# FPGA_GPIO.net
KiCad netlist of a schematic drawn in Altium Designer
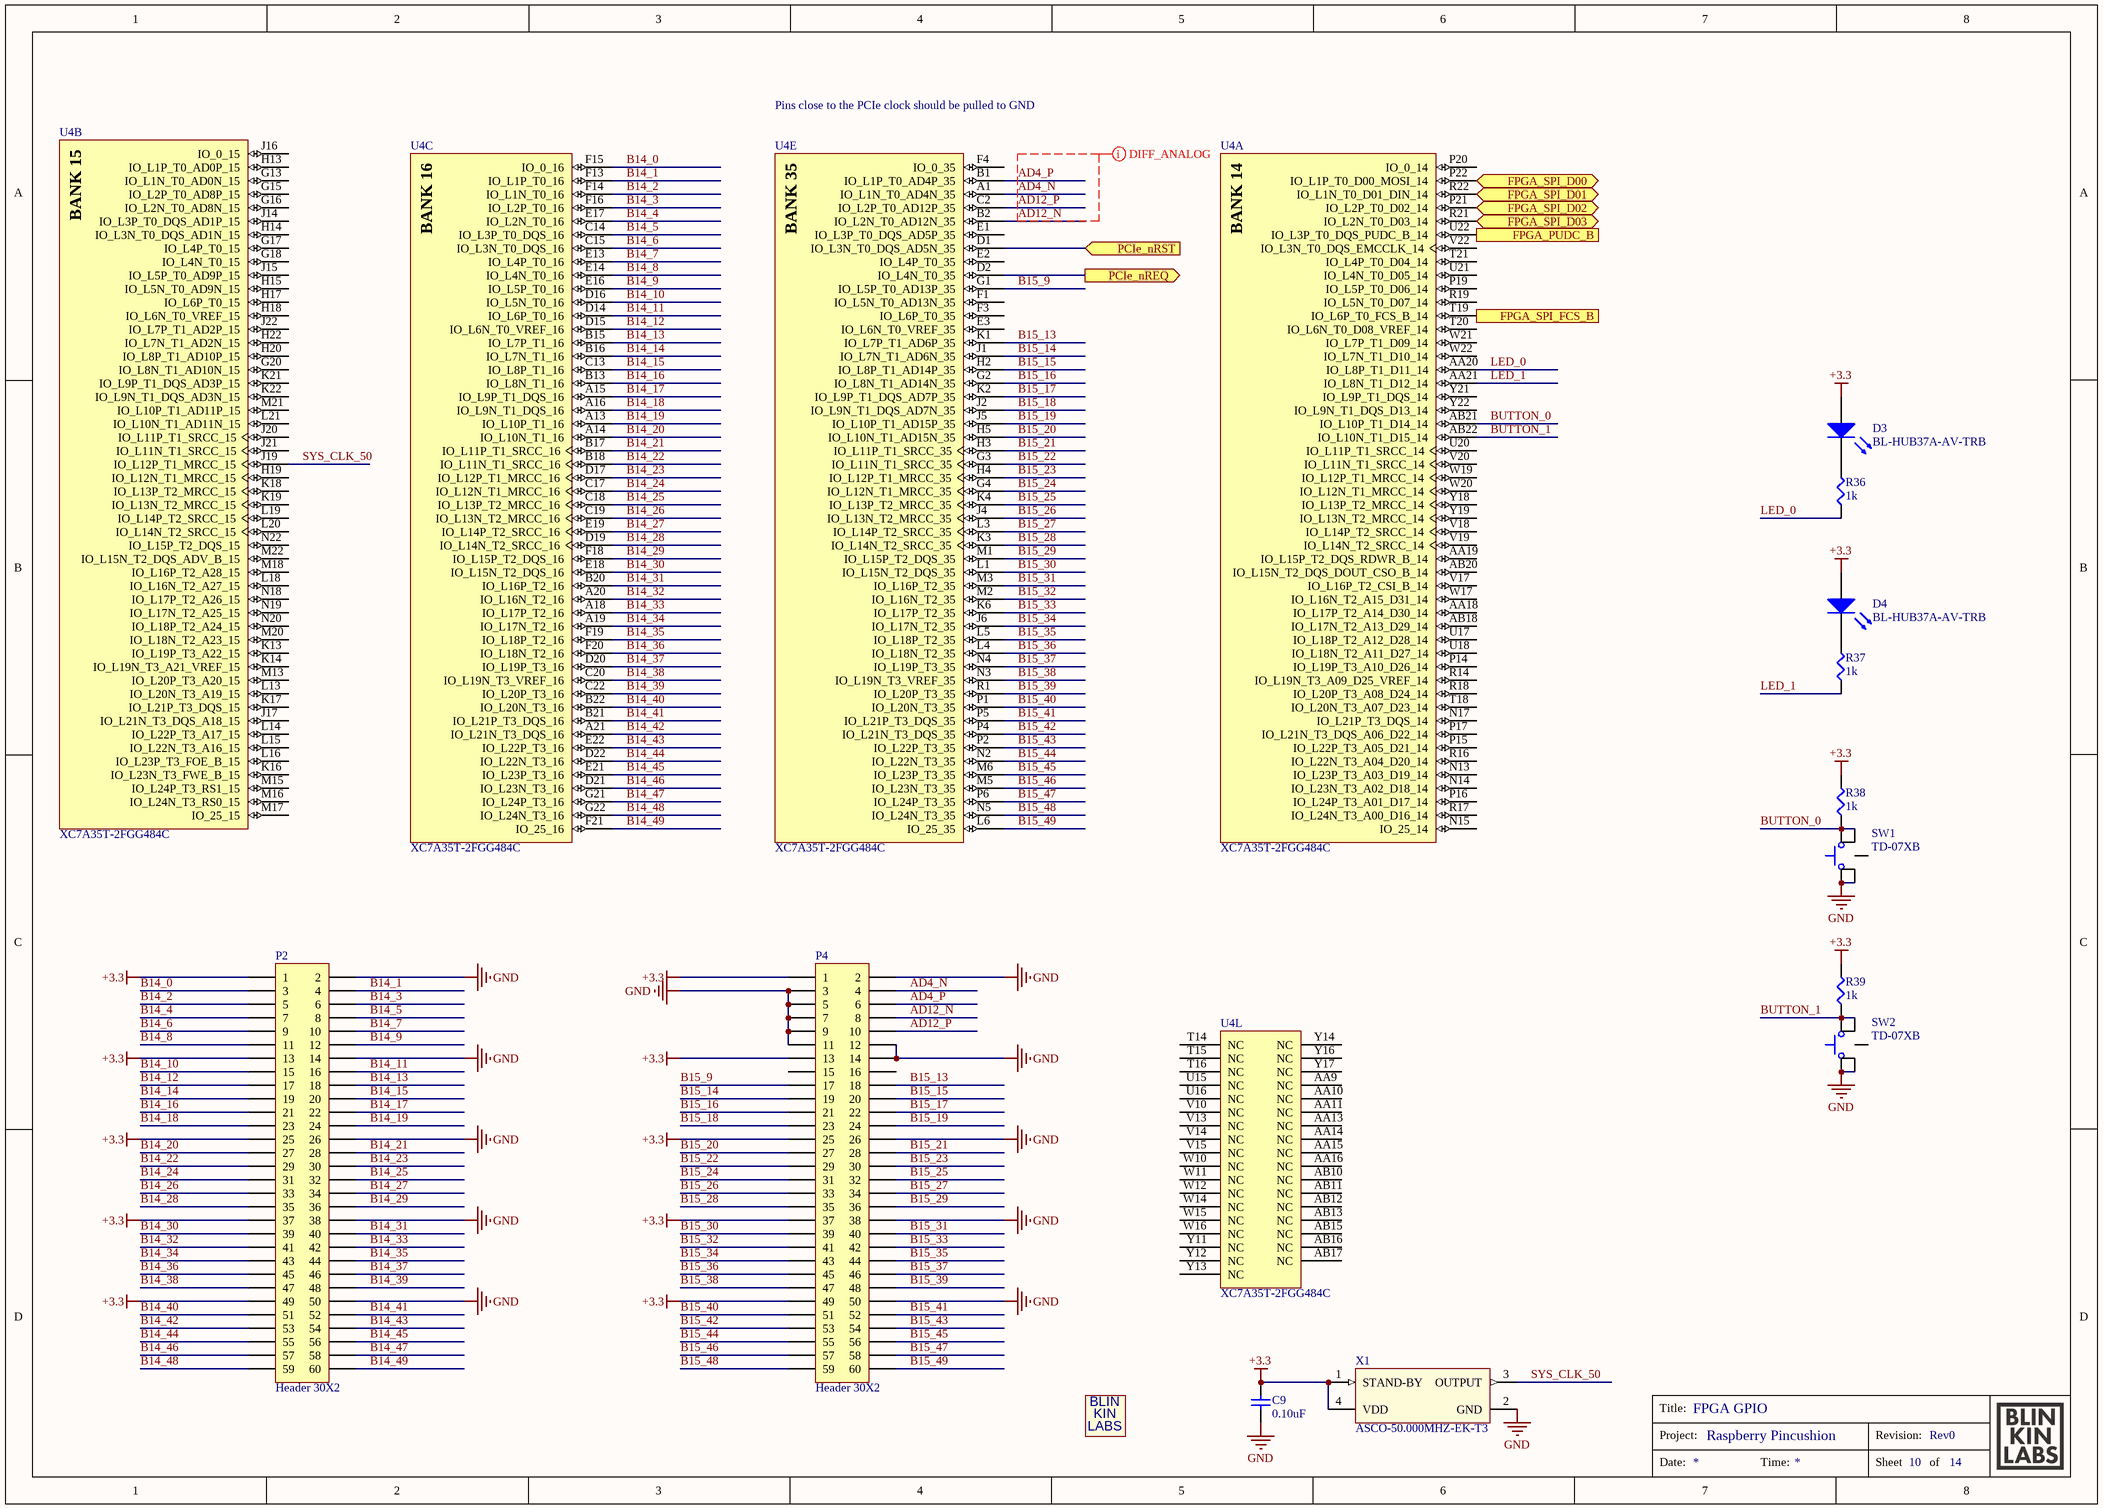
[diagram p0: FPGA GPIO.SchDoc]

(export (version "E")
  (design (tool "Eeschema 10.0.6"))
  (components
    (comp (ref "C9")
      (value "0.10uF")
      (footprint "CAPC1005X06L")
      (description "CAP CER 0.1UF 10V X5R 0402")
      (fields
        (field (name "PARTNUMBER") "GRM155R61A104KA01D")
        (field (name "DIGI-KEY PART NUMBER") "490-1318-1-ND")
      )
      (libsource (lib "cap_murata") (part "CAPACITOR"))
    )
    (comp (ref "D3")
      (value "BL-HUB37A-AV-TRB")
      (footprint "BL-Hxx37A-AV-TRB")
      (description "LED, 0402, Super Red, 50mcd@20mA, 627~637nm")
      (fields (field (name "MANUFACTURER") "BrtLed(佰鸿)") (field (name "LCSC PARTNUMBER") "C165980"))
      (libsource (lib "Blinkinlabs") (part "BL-HUB37A-AV-TRB"))
    )
    (comp (ref "D4")
      (value "BL-HUB37A-AV-TRB")
      (footprint "BL-Hxx37A-AV-TRB")
      (description "LED, 0402, Super Red, 50mcd@20mA, 627~637nm")
      (fields (field (name "MANUFACTURER") "BrtLed(佰鸿)") (field (name "LCSC PARTNUMBER") "C165980"))
      (libsource (lib "Blinkinlabs") (part "BL-HUB37A-AV-TRB"))
    )
    (comp (ref "L1")
      (value "BLINKINLABS_LOGO")
      (footprint "BLINKINLABS_LOGO")
      (description "Square logo")
      (libsource (lib "Blinkinlabs") (part "BLINKINLABS_LOGO"))
    )
    (comp (ref "P2")
      (value "Header 30X2")
      (footprint "HDR2X30")
      (description "Header, 30-Pin, Dual row")
      (fields (field (name "PUBLISHER") "Altium Limited"))
      (libsource (lib "Miscellaneous Connectors") (part "Header 30X2"))
    )
    (comp (ref "P4")
      (value "Header 30X2")
      (footprint "HDR2X30")
      (description "Header, 30-Pin, Dual row")
      (fields (field (name "PUBLISHER") "Altium Limited"))
      (libsource (lib "Miscellaneous Connectors") (part "Header 30X2"))
    )
    (comp (ref "R36")
      (value "1k")
      (footprint "ERJ2G(0402)_L")
      (description "RES SMD 1K OHM 5% 1/10W 0402")
      (fields (field (name "PARTNUMBER") "ERJ-2GEJ102X") (field (name "DIGI-KEY PART NUMBER") "P1.0KJCT-ND"))
      (libsource (lib "res_panasonic_erj_xls") (part "RESISTOR"))
    )
    (comp (ref "R37")
      (value "1k")
      (footprint "ERJ2G(0402)_L")
      (description "RES SMD 1K OHM 5% 1/10W 0402")
      (fields (field (name "PARTNUMBER") "ERJ-2GEJ102X") (field (name "DIGI-KEY PART NUMBER") "P1.0KJCT-ND"))
      (libsource (lib "res_panasonic_erj_xls") (part "RESISTOR"))
    )
    (comp (ref "R38")
      (value "1k")
      (footprint "ERJ2G(0402)_L")
      (description "RES SMD 1K OHM 5% 1/10W 0402")
      (fields (field (name "PARTNUMBER") "ERJ-2GEJ102X") (field (name "DIGI-KEY PART NUMBER") "P1.0KJCT-ND"))
      (libsource (lib "res_panasonic_erj_xls") (part "RESISTOR"))
    )
    (comp (ref "R39")
      (value "1k")
      (footprint "ERJ2G(0402)_L")
      (description "RES SMD 1K OHM 5% 1/10W 0402")
      (fields (field (name "PARTNUMBER") "ERJ-2GEJ102X") (field (name "DIGI-KEY PART NUMBER") "P1.0KJCT-ND"))
      (libsource (lib "res_panasonic_erj_xls") (part "RESISTOR"))
    )
    (comp (ref "SW1")
      (value "TD-07XB")
      (footprint "TD-07XB")
      (description "Tact Switch")
      (fields (field (name "MANUFACTURER") "ShenZhen XieJia Electronics Co Ltd"))
      (libsource (lib "Blinkinlabs") (part "TD-07XB"))
    )
    (comp (ref "SW2")
      (value "TD-07XB")
      (footprint "TD-07XB")
      (description "Tact Switch")
      (fields (field (name "MANUFACTURER") "ShenZhen XieJia Electronics Co Ltd"))
      (libsource (lib "Blinkinlabs") (part "TD-07XB"))
    )
    (comp (ref "U4")
      (value "XC7A35T-2FGG484C")
      (footprint "FGG484")
      (description "Artix-7 FPGA, 250 User I/Os, 4 GTP, 484-Ball BGA, Speed Grade 2, Commercial Grade, Pb-Free")
      (fields (field (name "MANUFACTURER") "Xilinx"))
      (libsource (lib "Altium Content Vault") (part "XLNX-XC7A35T-FGG484"))
    )
    (comp (ref "X1")
      (value "ASCO-50.000MHZ-EK-T3")
      (footprint "ABRA-ASCO-50.000MHZ-EK-T3-4_V")
      (description "Crystal Clock Oscillator, 50 MHz, -20 to 70 degC, 1.6 x 1.2 x 0.7 mm SMD")
      (fields (field (name "MANUFACTURER") "Abracon"))
      (libsource (lib "Altium Content Vault") (part "ABRA-ASCO-50_000MHZ-EK-T3-4"))
    )
  )
  (nets
    (net (code "1") (name "+3.3") (class "Default")
      (node (ref "C9") (pin "2") (pinfunction "2_2") (pintype "passive"))
      (node (ref "D3") (pin "1") (pinfunction "1_1") (pintype "passive"))
      (node (ref "D4") (pin "1") (pinfunction "1_1") (pintype "passive"))
      (node (ref "P2") (pin "1") (pinfunction "1_1") (pintype "passive"))
      (node (ref "P2") (pin "13") (pinfunction "13_13") (pintype "passive"))
      (node (ref "P2") (pin "25") (pinfunction "25_25") (pintype "passive"))
      (node (ref "P2") (pin "37") (pinfunction "37_37") (pintype "passive"))
      (node (ref "P2") (pin "49") (pinfunction "49_49") (pintype "passive"))
      (node (ref "P4") (pin "1") (pinfunction "1_1") (pintype "passive"))
      (node (ref "P4") (pin "13") (pinfunction "13_13") (pintype "passive"))
      (node (ref "P4") (pin "25") (pinfunction "25_25") (pintype "passive"))
      (node (ref "P4") (pin "37") (pinfunction "37_37") (pintype "passive"))
      (node (ref "P4") (pin "49") (pinfunction "49_49") (pintype "passive"))
      (node (ref "R38") (pin "2") (pinfunction "2_2") (pintype "passive"))
      (node (ref "R39") (pin "2") (pinfunction "2_2") (pintype "passive"))
      (node (ref "X1") (pin "1") (pinfunction "STAND-BY_1") (pintype "input"))
      (node (ref "X1") (pin "4") (pinfunction "VDD_4") (pintype "power_in"))
    )
    (net (code "2") (name "/AD4_N") (class "Default")
      (node (ref "P4") (pin "4") (pinfunction "4_4") (pintype "passive"))
      (node (ref "U4") (pin "A1") (pinfunction "IO_L1N_T0_AD4N_35_A1") (pintype "bidirectional"))
    )
    (net (code "3") (name "/AD4_P") (class "Default")
      (node (ref "P4") (pin "6") (pinfunction "6_6") (pintype "passive"))
      (node (ref "U4") (pin "B1") (pinfunction "IO_L1P_T0_AD4P_35_B1") (pintype "bidirectional"))
    )
    (net (code "4") (name "/AD12_N") (class "Default")
      (node (ref "P4") (pin "8") (pinfunction "8_8") (pintype "passive"))
      (node (ref "U4") (pin "B2") (pinfunction "IO_L2N_T0_AD12N_35_B2") (pintype "bidirectional"))
    )
    (net (code "5") (name "/AD12_P") (class "Default")
      (node (ref "P4") (pin "10") (pinfunction "10_10") (pintype "passive"))
      (node (ref "U4") (pin "C2") (pinfunction "IO_L2P_T0_AD12P_35_C2") (pintype "bidirectional"))
    )
    (net (code "6") (name "/B14_0") (class "Default")
      (node (ref "P2") (pin "3") (pinfunction "3_3") (pintype "passive"))
      (node (ref "U4") (pin "F15") (pinfunction "IO_0_16_F15") (pintype "bidirectional"))
    )
    (net (code "7") (name "/B14_1") (class "Default")
      (node (ref "P2") (pin "4") (pinfunction "4_4") (pintype "passive"))
      (node (ref "U4") (pin "F13") (pinfunction "IO_L1P_T0_16_F13") (pintype "bidirectional"))
    )
    (net (code "8") (name "/B14_2") (class "Default")
      (node (ref "P2") (pin "5") (pinfunction "5_5") (pintype "passive"))
      (node (ref "U4") (pin "F14") (pinfunction "IO_L1N_T0_16_F14") (pintype "bidirectional"))
    )
    (net (code "9") (name "/B14_3") (class "Default")
      (node (ref "P2") (pin "6") (pinfunction "6_6") (pintype "passive"))
      (node (ref "U4") (pin "F16") (pinfunction "IO_L2P_T0_16_F16") (pintype "bidirectional"))
    )
    (net (code "10") (name "/B14_4") (class "Default")
      (node (ref "P2") (pin "7") (pinfunction "7_7") (pintype "passive"))
      (node (ref "U4") (pin "E17") (pinfunction "IO_L2N_T0_16_E17") (pintype "bidirectional"))
    )
    (net (code "11") (name "/B14_5") (class "Default")
      (node (ref "P2") (pin "8") (pinfunction "8_8") (pintype "passive"))
      (node (ref "U4") (pin "C14") (pinfunction "IO_L3P_T0_DQS_16_C14") (pintype "bidirectional"))
    )
    (net (code "12") (name "/B14_6") (class "Default")
      (node (ref "P2") (pin "9") (pinfunction "9_9") (pintype "passive"))
      (node (ref "U4") (pin "C15") (pinfunction "IO_L3N_T0_DQS_16_C15") (pintype "bidirectional"))
    )
    (net (code "13") (name "/B14_7") (class "Default")
      (node (ref "P2") (pin "10") (pinfunction "10_10") (pintype "passive"))
      (node (ref "U4") (pin "E13") (pinfunction "IO_L4P_T0_16_E13") (pintype "bidirectional"))
    )
    (net (code "14") (name "/B14_8") (class "Default")
      (node (ref "P2") (pin "11") (pinfunction "11_11") (pintype "passive"))
      (node (ref "U4") (pin "E14") (pinfunction "IO_L4N_T0_16_E14") (pintype "bidirectional"))
    )
    (net (code "15") (name "/B14_9") (class "Default")
      (node (ref "P2") (pin "12") (pinfunction "12_12") (pintype "passive"))
      (node (ref "U4") (pin "E16") (pinfunction "IO_L5P_T0_16_E16") (pintype "bidirectional"))
    )
    (net (code "16") (name "/B14_10") (class "Default")
      (node (ref "P2") (pin "15") (pinfunction "15_15") (pintype "passive"))
      (node (ref "U4") (pin "D16") (pinfunction "IO_L5N_T0_16_D16") (pintype "bidirectional"))
    )
    (net (code "17") (name "/B14_11") (class "Default")
      (node (ref "P2") (pin "16") (pinfunction "16_16") (pintype "passive"))
      (node (ref "U4") (pin "D14") (pinfunction "IO_L6P_T0_16_D14") (pintype "bidirectional"))
    )
    (net (code "18") (name "/B14_12") (class "Default")
      (node (ref "P2") (pin "17") (pinfunction "17_17") (pintype "passive"))
      (node (ref "U4") (pin "D15") (pinfunction "IO_L6N_T0_VREF_16_D15") (pintype "bidirectional"))
    )
    (net (code "19") (name "/B14_13") (class "Default")
      (node (ref "P2") (pin "18") (pinfunction "18_18") (pintype "passive"))
      (node (ref "U4") (pin "B15") (pinfunction "IO_L7P_T1_16_B15") (pintype "bidirectional"))
    )
    (net (code "20") (name "/B14_14") (class "Default")
      (node (ref "P2") (pin "19") (pinfunction "19_19") (pintype "passive"))
      (node (ref "U4") (pin "B16") (pinfunction "IO_L7N_T1_16_B16") (pintype "bidirectional"))
    )
    (net (code "21") (name "/B14_15") (class "Default")
      (node (ref "P2") (pin "20") (pinfunction "20_20") (pintype "passive"))
      (node (ref "U4") (pin "C13") (pinfunction "IO_L8P_T1_16_C13") (pintype "bidirectional"))
    )
    (net (code "22") (name "/B14_16") (class "Default")
      (node (ref "P2") (pin "21") (pinfunction "21_21") (pintype "passive"))
      (node (ref "U4") (pin "B13") (pinfunction "IO_L8N_T1_16_B13") (pintype "bidirectional"))
    )
    (net (code "23") (name "/B14_17") (class "Default")
      (node (ref "P2") (pin "22") (pinfunction "22_22") (pintype "passive"))
      (node (ref "U4") (pin "A15") (pinfunction "IO_L9P_T1_DQS_16_A15") (pintype "bidirectional"))
    )
    (net (code "24") (name "/B14_18") (class "Default")
      (node (ref "P2") (pin "23") (pinfunction "23_23") (pintype "passive"))
      (node (ref "U4") (pin "A16") (pinfunction "IO_L9N_T1_DQS_16_A16") (pintype "bidirectional"))
    )
    (net (code "25") (name "/B14_19") (class "Default")
      (node (ref "P2") (pin "24") (pinfunction "24_24") (pintype "passive"))
      (node (ref "U4") (pin "A13") (pinfunction "IO_L10P_T1_16_A13") (pintype "bidirectional"))
    )
    (net (code "26") (name "/B14_20") (class "Default")
      (node (ref "P2") (pin "27") (pinfunction "27_27") (pintype "passive"))
      (node (ref "U4") (pin "A14") (pinfunction "IO_L10N_T1_16_A14") (pintype "bidirectional"))
    )
    (net (code "27") (name "/B14_21") (class "Default")
      (node (ref "P2") (pin "28") (pinfunction "28_28") (pintype "passive"))
      (node (ref "U4") (pin "B17") (pinfunction "IO_L11P_T1_SRCC_16_B17") (pintype "bidirectional"))
    )
    (net (code "28") (name "/B14_22") (class "Default")
      (node (ref "P2") (pin "29") (pinfunction "29_29") (pintype "passive"))
      (node (ref "U4") (pin "B18") (pinfunction "IO_L11N_T1_SRCC_16_B18") (pintype "bidirectional"))
    )
    (net (code "29") (name "/B14_23") (class "Default")
      (node (ref "P2") (pin "30") (pinfunction "30_30") (pintype "passive"))
      (node (ref "U4") (pin "D17") (pinfunction "IO_L12P_T1_MRCC_16_D17") (pintype "bidirectional"))
    )
    (net (code "30") (name "/B14_24") (class "Default")
      (node (ref "P2") (pin "31") (pinfunction "31_31") (pintype "passive"))
      (node (ref "U4") (pin "C17") (pinfunction "IO_L12N_T1_MRCC_16_C17") (pintype "bidirectional"))
    )
    (net (code "31") (name "/B14_25") (class "Default")
      (node (ref "P2") (pin "32") (pinfunction "32_32") (pintype "passive"))
      (node (ref "U4") (pin "C18") (pinfunction "IO_L13P_T2_MRCC_16_C18") (pintype "bidirectional"))
    )
    (net (code "32") (name "/B14_26") (class "Default")
      (node (ref "P2") (pin "33") (pinfunction "33_33") (pintype "passive"))
      (node (ref "U4") (pin "C19") (pinfunction "IO_L13N_T2_MRCC_16_C19") (pintype "bidirectional"))
    )
    (net (code "33") (name "/B14_27") (class "Default")
      (node (ref "P2") (pin "34") (pinfunction "34_34") (pintype "passive"))
      (node (ref "U4") (pin "E19") (pinfunction "IO_L14P_T2_SRCC_16_E19") (pintype "bidirectional"))
    )
    (net (code "34") (name "/B14_28") (class "Default")
      (node (ref "P2") (pin "35") (pinfunction "35_35") (pintype "passive"))
      (node (ref "U4") (pin "D19") (pinfunction "IO_L14N_T2_SRCC_16_D19") (pintype "bidirectional"))
    )
    (net (code "35") (name "/B14_29") (class "Default")
      (node (ref "P2") (pin "36") (pinfunction "36_36") (pintype "passive"))
      (node (ref "U4") (pin "F18") (pinfunction "IO_L15P_T2_DQS_16_F18") (pintype "bidirectional"))
    )
    (net (code "36") (name "/B14_30") (class "Default")
      (node (ref "P2") (pin "39") (pinfunction "39_39") (pintype "passive"))
      (node (ref "U4") (pin "E18") (pinfunction "IO_L15N_T2_DQS_16_E18") (pintype "bidirectional"))
    )
    (net (code "37") (name "/B14_31") (class "Default")
      (node (ref "P2") (pin "40") (pinfunction "40_40") (pintype "passive"))
      (node (ref "U4") (pin "B20") (pinfunction "IO_L16P_T2_16_B20") (pintype "bidirectional"))
    )
    (net (code "38") (name "/B14_32") (class "Default")
      (node (ref "P2") (pin "41") (pinfunction "41_41") (pintype "passive"))
      (node (ref "U4") (pin "A20") (pinfunction "IO_L16N_T2_16_A20") (pintype "bidirectional"))
    )
    (net (code "39") (name "/B14_33") (class "Default")
      (node (ref "P2") (pin "42") (pinfunction "42_42") (pintype "passive"))
      (node (ref "U4") (pin "A18") (pinfunction "IO_L17P_T2_16_A18") (pintype "bidirectional"))
    )
    (net (code "40") (name "/B14_34") (class "Default")
      (node (ref "P2") (pin "43") (pinfunction "43_43") (pintype "passive"))
      (node (ref "U4") (pin "A19") (pinfunction "IO_L17N_T2_16_A19") (pintype "bidirectional"))
    )
    (net (code "41") (name "/B14_35") (class "Default")
      (node (ref "P2") (pin "44") (pinfunction "44_44") (pintype "passive"))
      (node (ref "U4") (pin "F19") (pinfunction "IO_L18P_T2_16_F19") (pintype "bidirectional"))
    )
    (net (code "42") (name "/B14_36") (class "Default")
      (node (ref "P2") (pin "45") (pinfunction "45_45") (pintype "passive"))
      (node (ref "U4") (pin "F20") (pinfunction "IO_L18N_T2_16_F20") (pintype "bidirectional"))
    )
    (net (code "43") (name "/B14_37") (class "Default")
      (node (ref "P2") (pin "46") (pinfunction "46_46") (pintype "passive"))
      (node (ref "U4") (pin "D20") (pinfunction "IO_L19P_T3_16_D20") (pintype "bidirectional"))
    )
    (net (code "44") (name "/B14_38") (class "Default")
      (node (ref "P2") (pin "47") (pinfunction "47_47") (pintype "passive"))
      (node (ref "U4") (pin "C20") (pinfunction "IO_L19N_T3_VREF_16_C20") (pintype "bidirectional"))
    )
    (net (code "45") (name "/B14_39") (class "Default")
      (node (ref "P2") (pin "48") (pinfunction "48_48") (pintype "passive"))
      (node (ref "U4") (pin "C22") (pinfunction "IO_L20P_T3_16_C22") (pintype "bidirectional"))
    )
    (net (code "46") (name "/B14_40") (class "Default")
      (node (ref "P2") (pin "51") (pinfunction "51_51") (pintype "passive"))
      (node (ref "U4") (pin "B22") (pinfunction "IO_L20N_T3_16_B22") (pintype "bidirectional"))
    )
    (net (code "47") (name "/B14_41") (class "Default")
      (node (ref "P2") (pin "52") (pinfunction "52_52") (pintype "passive"))
      (node (ref "U4") (pin "B21") (pinfunction "IO_L21P_T3_DQS_16_B21") (pintype "bidirectional"))
    )
    (net (code "48") (name "/B14_42") (class "Default")
      (node (ref "P2") (pin "53") (pinfunction "53_53") (pintype "passive"))
      (node (ref "U4") (pin "A21") (pinfunction "IO_L21N_T3_DQS_16_A21") (pintype "bidirectional"))
    )
    (net (code "49") (name "/B14_43") (class "Default")
      (node (ref "P2") (pin "54") (pinfunction "54_54") (pintype "passive"))
      (node (ref "U4") (pin "E22") (pinfunction "IO_L22P_T3_16_E22") (pintype "bidirectional"))
    )
    (net (code "50") (name "/B14_44") (class "Default")
      (node (ref "P2") (pin "55") (pinfunction "55_55") (pintype "passive"))
      (node (ref "U4") (pin "D22") (pinfunction "IO_L22N_T3_16_D22") (pintype "bidirectional"))
    )
    (net (code "51") (name "/B14_45") (class "Default")
      (node (ref "P2") (pin "56") (pinfunction "56_56") (pintype "passive"))
      (node (ref "U4") (pin "E21") (pinfunction "IO_L23P_T3_16_E21") (pintype "bidirectional"))
    )
    (net (code "52") (name "/B14_46") (class "Default")
      (node (ref "P2") (pin "57") (pinfunction "57_57") (pintype "passive"))
      (node (ref "U4") (pin "D21") (pinfunction "IO_L23N_T3_16_D21") (pintype "bidirectional"))
    )
    (net (code "53") (name "/B14_47") (class "Default")
      (node (ref "P2") (pin "58") (pinfunction "58_58") (pintype "passive"))
      (node (ref "U4") (pin "G21") (pinfunction "IO_L24P_T3_16_G21") (pintype "bidirectional"))
    )
    (net (code "54") (name "/B14_48") (class "Default")
      (node (ref "P2") (pin "59") (pinfunction "59_59") (pintype "passive"))
      (node (ref "U4") (pin "G22") (pinfunction "IO_L24N_T3_16_G22") (pintype "bidirectional"))
    )
    (net (code "55") (name "/B14_49") (class "Default")
      (node (ref "P2") (pin "60") (pinfunction "60_60") (pintype "passive"))
      (node (ref "U4") (pin "F21") (pinfunction "IO_25_16_F21") (pintype "bidirectional"))
    )
    (net (code "56") (name "/B15_9") (class "Default")
      (node (ref "P4") (pin "17") (pinfunction "17_17") (pintype "passive"))
      (node (ref "U4") (pin "G1") (pinfunction "IO_L5P_T0_AD13P_35_G1") (pintype "bidirectional"))
    )
    (net (code "57") (name "/B15_13") (class "Default")
      (node (ref "P4") (pin "18") (pinfunction "18_18") (pintype "passive"))
      (node (ref "U4") (pin "K1") (pinfunction "IO_L7P_T1_AD6P_35_K1") (pintype "bidirectional"))
    )
    (net (code "58") (name "/B15_14") (class "Default")
      (node (ref "P4") (pin "19") (pinfunction "19_19") (pintype "passive"))
      (node (ref "U4") (pin "J1") (pinfunction "IO_L7N_T1_AD6N_35_J1") (pintype "bidirectional"))
    )
    (net (code "59") (name "/B15_15") (class "Default")
      (node (ref "P4") (pin "20") (pinfunction "20_20") (pintype "passive"))
      (node (ref "U4") (pin "H2") (pinfunction "IO_L8P_T1_AD14P_35_H2") (pintype "bidirectional"))
    )
    (net (code "60") (name "/B15_16") (class "Default")
      (node (ref "P4") (pin "21") (pinfunction "21_21") (pintype "passive"))
      (node (ref "U4") (pin "G2") (pinfunction "IO_L8N_T1_AD14N_35_G2") (pintype "bidirectional"))
    )
    (net (code "61") (name "/B15_17") (class "Default")
      (node (ref "P4") (pin "22") (pinfunction "22_22") (pintype "passive"))
      (node (ref "U4") (pin "K2") (pinfunction "IO_L9P_T1_DQS_AD7P_35_K2") (pintype "bidirectional"))
    )
    (net (code "62") (name "/B15_18") (class "Default")
      (node (ref "P4") (pin "23") (pinfunction "23_23") (pintype "passive"))
      (node (ref "U4") (pin "J2") (pinfunction "IO_L9N_T1_DQS_AD7N_35_J2") (pintype "bidirectional"))
    )
    (net (code "63") (name "/B15_19") (class "Default")
      (node (ref "P4") (pin "24") (pinfunction "24_24") (pintype "passive"))
      (node (ref "U4") (pin "J5") (pinfunction "IO_L10P_T1_AD15P_35_J5") (pintype "bidirectional"))
    )
    (net (code "64") (name "/B15_20") (class "Default")
      (node (ref "P4") (pin "27") (pinfunction "27_27") (pintype "passive"))
      (node (ref "U4") (pin "H5") (pinfunction "IO_L10N_T1_AD15N_35_H5") (pintype "bidirectional"))
    )
    (net (code "65") (name "/B15_21") (class "Default")
      (node (ref "P4") (pin "28") (pinfunction "28_28") (pintype "passive"))
      (node (ref "U4") (pin "H3") (pinfunction "IO_L11P_T1_SRCC_35_H3") (pintype "bidirectional"))
    )
    (net (code "66") (name "/B15_22") (class "Default")
      (node (ref "P4") (pin "29") (pinfunction "29_29") (pintype "passive"))
      (node (ref "U4") (pin "G3") (pinfunction "IO_L11N_T1_SRCC_35_G3") (pintype "bidirectional"))
    )
    (net (code "67") (name "/B15_23") (class "Default")
      (node (ref "P4") (pin "30") (pinfunction "30_30") (pintype "passive"))
      (node (ref "U4") (pin "H4") (pinfunction "IO_L12P_T1_MRCC_35_H4") (pintype "bidirectional"))
    )
    (net (code "68") (name "/B15_24") (class "Default")
      (node (ref "P4") (pin "31") (pinfunction "31_31") (pintype "passive"))
      (node (ref "U4") (pin "G4") (pinfunction "IO_L12N_T1_MRCC_35_G4") (pintype "bidirectional"))
    )
    (net (code "69") (name "/B15_25") (class "Default")
      (node (ref "P4") (pin "32") (pinfunction "32_32") (pintype "passive"))
      (node (ref "U4") (pin "K4") (pinfunction "IO_L13P_T2_MRCC_35_K4") (pintype "bidirectional"))
    )
    (net (code "70") (name "/B15_26") (class "Default")
      (node (ref "P4") (pin "33") (pinfunction "33_33") (pintype "passive"))
      (node (ref "U4") (pin "J4") (pinfunction "IO_L13N_T2_MRCC_35_J4") (pintype "bidirectional"))
    )
    (net (code "71") (name "/B15_27") (class "Default")
      (node (ref "P4") (pin "34") (pinfunction "34_34") (pintype "passive"))
      (node (ref "U4") (pin "L3") (pinfunction "IO_L14P_T2_SRCC_35_L3") (pintype "bidirectional"))
    )
    (net (code "72") (name "/B15_28") (class "Default")
      (node (ref "P4") (pin "35") (pinfunction "35_35") (pintype "passive"))
      (node (ref "U4") (pin "K3") (pinfunction "IO_L14N_T2_SRCC_35_K3") (pintype "bidirectional"))
    )
    (net (code "73") (name "/B15_29") (class "Default")
      (node (ref "P4") (pin "36") (pinfunction "36_36") (pintype "passive"))
      (node (ref "U4") (pin "M1") (pinfunction "IO_L15P_T2_DQS_35_M1") (pintype "bidirectional"))
    )
    (net (code "74") (name "/B15_30") (class "Default")
      (node (ref "P4") (pin "39") (pinfunction "39_39") (pintype "passive"))
      (node (ref "U4") (pin "L1") (pinfunction "IO_L15N_T2_DQS_35_L1") (pintype "bidirectional"))
    )
    (net (code "75") (name "/B15_31") (class "Default")
      (node (ref "P4") (pin "40") (pinfunction "40_40") (pintype "passive"))
      (node (ref "U4") (pin "M3") (pinfunction "IO_L16P_T2_35_M3") (pintype "bidirectional"))
    )
    (net (code "76") (name "/B15_32") (class "Default")
      (node (ref "P4") (pin "41") (pinfunction "41_41") (pintype "passive"))
      (node (ref "U4") (pin "M2") (pinfunction "IO_L16N_T2_35_M2") (pintype "bidirectional"))
    )
    (net (code "77") (name "/B15_33") (class "Default")
      (node (ref "P4") (pin "42") (pinfunction "42_42") (pintype "passive"))
      (node (ref "U4") (pin "K6") (pinfunction "IO_L17P_T2_35_K6") (pintype "bidirectional"))
    )
    (net (code "78") (name "/B15_34") (class "Default")
      (node (ref "P4") (pin "43") (pinfunction "43_43") (pintype "passive"))
      (node (ref "U4") (pin "J6") (pinfunction "IO_L17N_T2_35_J6") (pintype "bidirectional"))
    )
    (net (code "79") (name "/B15_35") (class "Default")
      (node (ref "P4") (pin "44") (pinfunction "44_44") (pintype "passive"))
      (node (ref "U4") (pin "L5") (pinfunction "IO_L18P_T2_35_L5") (pintype "bidirectional"))
    )
    (net (code "80") (name "/B15_36") (class "Default")
      (node (ref "P4") (pin "45") (pinfunction "45_45") (pintype "passive"))
      (node (ref "U4") (pin "L4") (pinfunction "IO_L18N_T2_35_L4") (pintype "bidirectional"))
    )
    (net (code "81") (name "/B15_37") (class "Default")
      (node (ref "P4") (pin "46") (pinfunction "46_46") (pintype "passive"))
      (node (ref "U4") (pin "N4") (pinfunction "IO_L19P_T3_35_N4") (pintype "bidirectional"))
    )
    (net (code "82") (name "/B15_38") (class "Default")
      (node (ref "P4") (pin "47") (pinfunction "47_47") (pintype "passive"))
      (node (ref "U4") (pin "N3") (pinfunction "IO_L19N_T3_VREF_35_N3") (pintype "bidirectional"))
    )
    (net (code "83") (name "/B15_39") (class "Default")
      (node (ref "P4") (pin "48") (pinfunction "48_48") (pintype "passive"))
      (node (ref "U4") (pin "R1") (pinfunction "IO_L20P_T3_35_R1") (pintype "bidirectional"))
    )
    (net (code "84") (name "/B15_40") (class "Default")
      (node (ref "P4") (pin "51") (pinfunction "51_51") (pintype "passive"))
      (node (ref "U4") (pin "P1") (pinfunction "IO_L20N_T3_35_P1") (pintype "bidirectional"))
    )
    (net (code "85") (name "/B15_41") (class "Default")
      (node (ref "P4") (pin "52") (pinfunction "52_52") (pintype "passive"))
      (node (ref "U4") (pin "P5") (pinfunction "IO_L21P_T3_DQS_35_P5") (pintype "bidirectional"))
    )
    (net (code "86") (name "/B15_42") (class "Default")
      (node (ref "P4") (pin "53") (pinfunction "53_53") (pintype "passive"))
      (node (ref "U4") (pin "P4") (pinfunction "IO_L21N_T3_DQS_35_P4") (pintype "bidirectional"))
    )
    (net (code "87") (name "/B15_43") (class "Default")
      (node (ref "P4") (pin "54") (pinfunction "54_54") (pintype "passive"))
      (node (ref "U4") (pin "P2") (pinfunction "IO_L22P_T3_35_P2") (pintype "bidirectional"))
    )
    (net (code "88") (name "/B15_44") (class "Default")
      (node (ref "P4") (pin "55") (pinfunction "55_55") (pintype "passive"))
      (node (ref "U4") (pin "N2") (pinfunction "IO_L22N_T3_35_N2") (pintype "bidirectional"))
    )
    (net (code "89") (name "/B15_45") (class "Default")
      (node (ref "P4") (pin "56") (pinfunction "56_56") (pintype "passive"))
      (node (ref "U4") (pin "M6") (pinfunction "IO_L23P_T3_35_M6") (pintype "bidirectional"))
    )
    (net (code "90") (name "/B15_46") (class "Default")
      (node (ref "P4") (pin "57") (pinfunction "57_57") (pintype "passive"))
      (node (ref "U4") (pin "M5") (pinfunction "IO_L23N_T3_35_M5") (pintype "bidirectional"))
    )
    (net (code "91") (name "/B15_47") (class "Default")
      (node (ref "P4") (pin "58") (pinfunction "58_58") (pintype "passive"))
      (node (ref "U4") (pin "P6") (pinfunction "IO_L24P_T3_35_P6") (pintype "bidirectional"))
    )
    (net (code "92") (name "/B15_48") (class "Default")
      (node (ref "P4") (pin "59") (pinfunction "59_59") (pintype "passive"))
      (node (ref "U4") (pin "N5") (pinfunction "IO_L24N_T3_35_N5") (pintype "bidirectional"))
    )
    (net (code "93") (name "/B15_49") (class "Default")
      (node (ref "P4") (pin "60") (pinfunction "60_60") (pintype "passive"))
      (node (ref "U4") (pin "L6") (pinfunction "IO_25_35_L6") (pintype "bidirectional"))
    )
    (net (code "94") (name "/BUTTON_0") (class "Default")
      (node (ref "R38") (pin "1") (pinfunction "1_1") (pintype "passive"))
      (node (ref "SW1") (pin "3") (pinfunction "3_3") (pintype "passive"))
      (node (ref "SW1") (pin "4") (pinfunction "4_4") (pintype "passive"))
      (node (ref "U4") (pin "AB21") (pinfunction "IO_L10P_T1_D14_14_AB21") (pintype "bidirectional"))
    )
    (net (code "95") (name "/BUTTON_1") (class "Default")
      (node (ref "R39") (pin "1") (pinfunction "1_1") (pintype "passive"))
      (node (ref "SW2") (pin "3") (pinfunction "3_3") (pintype "passive"))
      (node (ref "SW2") (pin "4") (pinfunction "4_4") (pintype "passive"))
      (node (ref "U4") (pin "AB22") (pinfunction "IO_L10N_T1_D15_14_AB22") (pintype "bidirectional"))
    )
    (net (code "96") (name "/FPGA_PUDC_B") (class "Default")
      (node (ref "U4") (pin "U22") (pinfunction "IO_L3P_T0_DQS_PUDC_B_14_U22") (pintype "bidirectional"))
    )
    (net (code "97") (name "/FPGA_SPI_D00") (class "Default")
      (node (ref "U4") (pin "P22") (pinfunction "IO_L1P_T0_D00_MOSI_14_P22") (pintype "bidirectional"))
    )
    (net (code "98") (name "/FPGA_SPI_D01") (class "Default")
      (node (ref "U4") (pin "R22") (pinfunction "IO_L1N_T0_D01_DIN_14_R22") (pintype "bidirectional"))
    )
    (net (code "99") (name "/FPGA_SPI_D02") (class "Default")
      (node (ref "U4") (pin "P21") (pinfunction "IO_L2P_T0_D02_14_P21") (pintype "bidirectional"))
    )
    (net (code "100") (name "/FPGA_SPI_D03") (class "Default")
      (node (ref "U4") (pin "R21") (pinfunction "IO_L2N_T0_D03_14_R21") (pintype "bidirectional"))
    )
    (net (code "101") (name "/FPGA_SPI_FCS_B") (class "Default")
      (node (ref "U4") (pin "T19") (pinfunction "IO_L6P_T0_FCS_B_14_T19") (pintype "bidirectional"))
    )
    (net (code "102") (name "/LED_0") (class "Default")
      (node (ref "R36") (pin "1") (pinfunction "1_1") (pintype "passive"))
      (node (ref "U4") (pin "AA20") (pinfunction "IO_L8P_T1_D11_14_AA20") (pintype "bidirectional"))
    )
    (net (code "103") (name "/LED_1") (class "Default")
      (node (ref "R37") (pin "1") (pinfunction "1_1") (pintype "passive"))
      (node (ref "U4") (pin "AA21") (pinfunction "IO_L8N_T1_D12_14_AA21") (pintype "bidirectional"))
    )
    (net (code "104") (name "/PCIe_nREQ") (class "Default")
      (node (ref "U4") (pin "D2") (pinfunction "IO_L4N_T0_35_D2") (pintype "bidirectional"))
    )
    (net (code "105") (name "/PCIe_nRST") (class "Default")
      (node (ref "U4") (pin "D1") (pinfunction "IO_L3N_T0_DQS_AD5N_35_D1") (pintype "bidirectional"))
    )
    (net (code "106") (name "/SYS_CLK_50") (class "Default")
      (node (ref "U4") (pin "J19") (pinfunction "IO_L12P_T1_MRCC_15_J19") (pintype "bidirectional"))
      (node (ref "X1") (pin "3") (pinfunction "OUTPUT_3") (pintype "output"))
    )
    (net (code "107") (name "GND") (class "Default")
      (node (ref "C9") (pin "1") (pinfunction "1_1") (pintype "passive"))
      (node (ref "P2") (pin "14") (pinfunction "14_14") (pintype "passive"))
      (node (ref "P2") (pin "2") (pinfunction "2_2") (pintype "passive"))
      (node (ref "P2") (pin "26") (pinfunction "26_26") (pintype "passive"))
      (node (ref "P2") (pin "38") (pinfunction "38_38") (pintype "passive"))
      (node (ref "P2") (pin "50") (pinfunction "50_50") (pintype "passive"))
      (node (ref "P4") (pin "11") (pinfunction "11_11") (pintype "passive"))
      (node (ref "P4") (pin "12") (pinfunction "12_12") (pintype "passive"))
      (node (ref "P4") (pin "14") (pinfunction "14_14") (pintype "passive"))
      (node (ref "P4") (pin "2") (pinfunction "2_2") (pintype "passive"))
      (node (ref "P4") (pin "26") (pinfunction "26_26") (pintype "passive"))
      (node (ref "P4") (pin "3") (pinfunction "3_3") (pintype "passive"))
      (node (ref "P4") (pin "38") (pinfunction "38_38") (pintype "passive"))
      (node (ref "P4") (pin "5") (pinfunction "5_5") (pintype "passive"))
      (node (ref "P4") (pin "50") (pinfunction "50_50") (pintype "passive"))
      (node (ref "P4") (pin "7") (pinfunction "7_7") (pintype "passive"))
      (node (ref "P4") (pin "9") (pinfunction "9_9") (pintype "passive"))
      (node (ref "SW1") (pin "1") (pinfunction "1_1") (pintype "passive"))
      (node (ref "SW1") (pin "2") (pinfunction "2_2") (pintype "passive"))
      (node (ref "SW2") (pin "1") (pinfunction "1_1") (pintype "passive"))
      (node (ref "SW2") (pin "2") (pinfunction "2_2") (pintype "passive"))
      (node (ref "X1") (pin "2") (pinfunction "GND_2") (pintype "power_in"))
    )
    (net (code "108") (name "Net-(D3-Pad2)") (class "Default")
      (node (ref "D3") (pin "2") (pinfunction "2_2") (pintype "passive"))
      (node (ref "R36") (pin "2") (pinfunction "2_2") (pintype "passive"))
    )
    (net (code "109") (name "Net-(D4-Pad2)") (class "Default")
      (node (ref "D4") (pin "2") (pinfunction "2_2") (pintype "passive"))
      (node (ref "R37") (pin "2") (pinfunction "2_2") (pintype "passive"))
    )
    (net (code "110") (name "unconnected-(P4-Pad15)") (class "Default")
      (node (ref "P4") (pin "15") (pinfunction "15_15") (pintype "passive"))
    )
    (net (code "111") (name "unconnected-(P4-Pad16)") (class "Default")
      (node (ref "P4") (pin "16") (pinfunction "16_16") (pintype "passive"))
    )
    (net (code "112") (name "unconnected-(SW1-Pad5)") (class "Default")
      (node (ref "SW1") (pin "5") (pinfunction "5_5") (pintype "passive"))
    )
    (net (code "113") (name "unconnected-(SW2-Pad5)") (class "Default")
      (node (ref "SW2") (pin "5") (pinfunction "5_5") (pintype "passive"))
    )
    (net (code "114") (name "unconnected-(U4A-IO_0_14-PadP20)") (class "Default")
      (node (ref "U4") (pin "P20") (pinfunction "IO_0_14_P20") (pintype "bidirectional"))
    )
    (net (code "115") (name "unconnected-(U4A-IO_25_14-PadN15)") (class "Default")
      (node (ref "U4") (pin "N15") (pinfunction "IO_25_14_N15") (pintype "bidirectional"))
    )
    (net (code "116") (name "unconnected-(U4A-IO_L3N_T0_DQS_EMCCLK_14-PadV22)") (class "Default")
      (node (ref "U4") (pin "V22") (pinfunction "IO_L3N_T0_DQS_EMCCLK_14_V22") (pintype "bidirectional"))
    )
    (net (code "117") (name "unconnected-(U4A-IO_L4N_T0_D05_14-PadU21)") (class "Default")
      (node (ref "U4") (pin "U21") (pinfunction "IO_L4N_T0_D05_14_U21") (pintype "bidirectional"))
    )
    (net (code "118") (name "unconnected-(U4A-IO_L4P_T0_D04_14-PadT21)") (class "Default")
      (node (ref "U4") (pin "T21") (pinfunction "IO_L4P_T0_D04_14_T21") (pintype "bidirectional"))
    )
    (net (code "119") (name "unconnected-(U4A-IO_L5N_T0_D07_14-PadR19)") (class "Default")
      (node (ref "U4") (pin "R19") (pinfunction "IO_L5N_T0_D07_14_R19") (pintype "bidirectional"))
    )
    (net (code "120") (name "unconnected-(U4A-IO_L5P_T0_D06_14-PadP19)") (class "Default")
      (node (ref "U4") (pin "P19") (pinfunction "IO_L5P_T0_D06_14_P19") (pintype "bidirectional"))
    )
    (net (code "121") (name "unconnected-(U4A-IO_L6N_T0_D08_VREF_14-PadT20)") (class "Default")
      (node (ref "U4") (pin "T20") (pinfunction "IO_L6N_T0_D08_VREF_14_T20") (pintype "bidirectional"))
    )
    (net (code "122") (name "unconnected-(U4A-IO_L7N_T1_D10_14-PadW22)") (class "Default")
      (node (ref "U4") (pin "W22") (pinfunction "IO_L7N_T1_D10_14_W22") (pintype "bidirectional"))
    )
    (net (code "123") (name "unconnected-(U4A-IO_L7P_T1_D09_14-PadW21)") (class "Default")
      (node (ref "U4") (pin "W21") (pinfunction "IO_L7P_T1_D09_14_W21") (pintype "bidirectional"))
    )
    (net (code "124") (name "unconnected-(U4A-IO_L9N_T1_DQS_D13_14-PadY22)") (class "Default")
      (node (ref "U4") (pin "Y22") (pinfunction "IO_L9N_T1_DQS_D13_14_Y22") (pintype "bidirectional"))
    )
    (net (code "125") (name "unconnected-(U4A-IO_L9P_T1_DQS_14-PadY21)") (class "Default")
      (node (ref "U4") (pin "Y21") (pinfunction "IO_L9P_T1_DQS_14_Y21") (pintype "bidirectional"))
    )
    (net (code "126") (name "unconnected-(U4A-IO_L11N_T1_SRCC_14-PadV20)") (class "Default")
      (node (ref "U4") (pin "V20") (pinfunction "IO_L11N_T1_SRCC_14_V20") (pintype "bidirectional"))
    )
    (net (code "127") (name "unconnected-(U4A-IO_L11P_T1_SRCC_14-PadU20)") (class "Default")
      (node (ref "U4") (pin "U20") (pinfunction "IO_L11P_T1_SRCC_14_U20") (pintype "bidirectional"))
    )
    (net (code "128") (name "unconnected-(U4A-IO_L12N_T1_MRCC_14-PadW20)") (class "Default")
      (node (ref "U4") (pin "W20") (pinfunction "IO_L12N_T1_MRCC_14_W20") (pintype "bidirectional"))
    )
    (net (code "129") (name "unconnected-(U4A-IO_L12P_T1_MRCC_14-PadW19)") (class "Default")
      (node (ref "U4") (pin "W19") (pinfunction "IO_L12P_T1_MRCC_14_W19") (pintype "bidirectional"))
    )
    (net (code "130") (name "unconnected-(U4A-IO_L13N_T2_MRCC_14-PadY19)") (class "Default")
      (node (ref "U4") (pin "Y19") (pinfunction "IO_L13N_T2_MRCC_14_Y19") (pintype "bidirectional"))
    )
    (net (code "131") (name "unconnected-(U4A-IO_L13P_T2_MRCC_14-PadY18)") (class "Default")
      (node (ref "U4") (pin "Y18") (pinfunction "IO_L13P_T2_MRCC_14_Y18") (pintype "bidirectional"))
    )
    (net (code "132") (name "unconnected-(U4A-IO_L14N_T2_SRCC_14-PadV19)") (class "Default")
      (node (ref "U4") (pin "V19") (pinfunction "IO_L14N_T2_SRCC_14_V19") (pintype "bidirectional"))
    )
    (net (code "133") (name "unconnected-(U4A-IO_L14P_T2_SRCC_14-PadV18)") (class "Default")
      (node (ref "U4") (pin "V18") (pinfunction "IO_L14P_T2_SRCC_14_V18") (pintype "bidirectional"))
    )
    (net (code "134") (name "unconnected-(U4A-IO_L15N_T2_DQS_DOUT_CSO_B_14-PadAB20)") (class "Default")
      (node (ref "U4") (pin "AB20") (pinfunction "IO_L15N_T2_DQS_DOUT_CSO_B_14_AB20") (pintype "bidirectional"))
    )
    (net (code "135") (name "unconnected-(U4A-IO_L15P_T2_DQS_RDWR_B_14-PadAA19)") (class "Default")
      (node (ref "U4") (pin "AA19") (pinfunction "IO_L15P_T2_DQS_RDWR_B_14_AA19") (pintype "bidirectional"))
    )
    (net (code "136") (name "unconnected-(U4A-IO_L16N_T2_A15_D31_14-PadW17)") (class "Default")
      (node (ref "U4") (pin "W17") (pinfunction "IO_L16N_T2_A15_D31_14_W17") (pintype "bidirectional"))
    )
    (net (code "137") (name "unconnected-(U4A-IO_L16P_T2_CSI_B_14-PadV17)") (class "Default")
      (node (ref "U4") (pin "V17") (pinfunction "IO_L16P_T2_CSI_B_14_V17") (pintype "bidirectional"))
    )
    (net (code "138") (name "unconnected-(U4A-IO_L17N_T2_A13_D29_14-PadAB18)") (class "Default")
      (node (ref "U4") (pin "AB18") (pinfunction "IO_L17N_T2_A13_D29_14_AB18") (pintype "bidirectional"))
    )
    (net (code "139") (name "unconnected-(U4A-IO_L17P_T2_A14_D30_14-PadAA18)") (class "Default")
      (node (ref "U4") (pin "AA18") (pinfunction "IO_L17P_T2_A14_D30_14_AA18") (pintype "bidirectional"))
    )
    (net (code "140") (name "unconnected-(U4A-IO_L18N_T2_A11_D27_14-PadU18)") (class "Default")
      (node (ref "U4") (pin "U18") (pinfunction "IO_L18N_T2_A11_D27_14_U18") (pintype "bidirectional"))
    )
    (net (code "141") (name "unconnected-(U4A-IO_L18P_T2_A12_D28_14-PadU17)") (class "Default")
      (node (ref "U4") (pin "U17") (pinfunction "IO_L18P_T2_A12_D28_14_U17") (pintype "bidirectional"))
    )
    (net (code "142") (name "unconnected-(U4A-IO_L19N_T3_A09_D25_VREF_14-PadR14)") (class "Default")
      (node (ref "U4") (pin "R14") (pinfunction "IO_L19N_T3_A09_D25_VREF_14_R14") (pintype "bidirectional"))
    )
    (net (code "143") (name "unconnected-(U4A-IO_L19P_T3_A10_D26_14-PadP14)") (class "Default")
      (node (ref "U4") (pin "P14") (pinfunction "IO_L19P_T3_A10_D26_14_P14") (pintype "bidirectional"))
    )
    (net (code "144") (name "unconnected-(U4A-IO_L20N_T3_A07_D23_14-PadT18)") (class "Default")
      (node (ref "U4") (pin "T18") (pinfunction "IO_L20N_T3_A07_D23_14_T18") (pintype "bidirectional"))
    )
    (net (code "145") (name "unconnected-(U4A-IO_L20P_T3_A08_D24_14-PadR18)") (class "Default")
      (node (ref "U4") (pin "R18") (pinfunction "IO_L20P_T3_A08_D24_14_R18") (pintype "bidirectional"))
    )
    (net (code "146") (name "unconnected-(U4A-IO_L21N_T3_DQS_A06_D22_14-PadP17)") (class "Default")
      (node (ref "U4") (pin "P17") (pinfunction "IO_L21N_T3_DQS_A06_D22_14_P17") (pintype "bidirectional"))
    )
    (net (code "147") (name "unconnected-(U4A-IO_L21P_T3_DQS_14-PadN17)") (class "Default")
      (node (ref "U4") (pin "N17") (pinfunction "IO_L21P_T3_DQS_14_N17") (pintype "bidirectional"))
    )
    (net (code "148") (name "unconnected-(U4A-IO_L22N_T3_A04_D20_14-PadR16)") (class "Default")
      (node (ref "U4") (pin "R16") (pinfunction "IO_L22N_T3_A04_D20_14_R16") (pintype "bidirectional"))
    )
    (net (code "149") (name "unconnected-(U4A-IO_L22P_T3_A05_D21_14-PadP15)") (class "Default")
      (node (ref "U4") (pin "P15") (pinfunction "IO_L22P_T3_A05_D21_14_P15") (pintype "bidirectional"))
    )
    (net (code "150") (name "unconnected-(U4A-IO_L23N_T3_A02_D18_14-PadN14)") (class "Default")
      (node (ref "U4") (pin "N14") (pinfunction "IO_L23N_T3_A02_D18_14_N14") (pintype "bidirectional"))
    )
    (net (code "151") (name "unconnected-(U4A-IO_L23P_T3_A03_D19_14-PadN13)") (class "Default")
      (node (ref "U4") (pin "N13") (pinfunction "IO_L23P_T3_A03_D19_14_N13") (pintype "bidirectional"))
    )
    (net (code "152") (name "unconnected-(U4A-IO_L24N_T3_A00_D16_14-PadR17)") (class "Default")
      (node (ref "U4") (pin "R17") (pinfunction "IO_L24N_T3_A00_D16_14_R17") (pintype "bidirectional"))
    )
    (net (code "153") (name "unconnected-(U4A-IO_L24P_T3_A01_D17_14-PadP16)") (class "Default")
      (node (ref "U4") (pin "P16") (pinfunction "IO_L24P_T3_A01_D17_14_P16") (pintype "bidirectional"))
    )
    (net (code "154") (name "unconnected-(U4B-IO_0_15-PadJ16)") (class "Default")
      (node (ref "U4") (pin "J16") (pinfunction "IO_0_15_J16") (pintype "bidirectional"))
    )
    (net (code "155") (name "unconnected-(U4B-IO_25_15-PadM17)") (class "Default")
      (node (ref "U4") (pin "M17") (pinfunction "IO_25_15_M17") (pintype "bidirectional"))
    )
    (net (code "156") (name "unconnected-(U4B-IO_L1N_T0_AD0N_15-PadG13)") (class "Default")
      (node (ref "U4") (pin "G13") (pinfunction "IO_L1N_T0_AD0N_15_G13") (pintype "bidirectional"))
    )
    (net (code "157") (name "unconnected-(U4B-IO_L1P_T0_AD0P_15-PadH13)") (class "Default")
      (node (ref "U4") (pin "H13") (pinfunction "IO_L1P_T0_AD0P_15_H13") (pintype "bidirectional"))
    )
    (net (code "158") (name "unconnected-(U4B-IO_L2N_T0_AD8N_15-PadG16)") (class "Default")
      (node (ref "U4") (pin "G16") (pinfunction "IO_L2N_T0_AD8N_15_G16") (pintype "bidirectional"))
    )
    (net (code "159") (name "unconnected-(U4B-IO_L2P_T0_AD8P_15-PadG15)") (class "Default")
      (node (ref "U4") (pin "G15") (pinfunction "IO_L2P_T0_AD8P_15_G15") (pintype "bidirectional"))
    )
    (net (code "160") (name "unconnected-(U4B-IO_L3N_T0_DQS_AD1N_15-PadH14)") (class "Default")
      (node (ref "U4") (pin "H14") (pinfunction "IO_L3N_T0_DQS_AD1N_15_H14") (pintype "bidirectional"))
    )
    (net (code "161") (name "unconnected-(U4B-IO_L3P_T0_DQS_AD1P_15-PadJ14)") (class "Default")
      (node (ref "U4") (pin "J14") (pinfunction "IO_L3P_T0_DQS_AD1P_15_J14") (pintype "bidirectional"))
    )
    (net (code "162") (name "unconnected-(U4B-IO_L4N_T0_15-PadG18)") (class "Default")
      (node (ref "U4") (pin "G18") (pinfunction "IO_L4N_T0_15_G18") (pintype "bidirectional"))
    )
    (net (code "163") (name "unconnected-(U4B-IO_L4P_T0_15-PadG17)") (class "Default")
      (node (ref "U4") (pin "G17") (pinfunction "IO_L4P_T0_15_G17") (pintype "bidirectional"))
    )
    (net (code "164") (name "unconnected-(U4B-IO_L5N_T0_AD9N_15-PadH15)") (class "Default")
      (node (ref "U4") (pin "H15") (pinfunction "IO_L5N_T0_AD9N_15_H15") (pintype "bidirectional"))
    )
    (net (code "165") (name "unconnected-(U4B-IO_L5P_T0_AD9P_15-PadJ15)") (class "Default")
      (node (ref "U4") (pin "J15") (pinfunction "IO_L5P_T0_AD9P_15_J15") (pintype "bidirectional"))
    )
    (net (code "166") (name "unconnected-(U4B-IO_L6N_T0_VREF_15-PadH18)") (class "Default")
      (node (ref "U4") (pin "H18") (pinfunction "IO_L6N_T0_VREF_15_H18") (pintype "bidirectional"))
    )
    (net (code "167") (name "unconnected-(U4B-IO_L6P_T0_15-PadH17)") (class "Default")
      (node (ref "U4") (pin "H17") (pinfunction "IO_L6P_T0_15_H17") (pintype "bidirectional"))
    )
    (net (code "168") (name "unconnected-(U4B-IO_L7N_T1_AD2N_15-PadH22)") (class "Default")
      (node (ref "U4") (pin "H22") (pinfunction "IO_L7N_T1_AD2N_15_H22") (pintype "bidirectional"))
    )
    (net (code "169") (name "unconnected-(U4B-IO_L7P_T1_AD2P_15-PadJ22)") (class "Default")
      (node (ref "U4") (pin "J22") (pinfunction "IO_L7P_T1_AD2P_15_J22") (pintype "bidirectional"))
    )
    (net (code "170") (name "unconnected-(U4B-IO_L8N_T1_AD10N_15-PadG20)") (class "Default")
      (node (ref "U4") (pin "G20") (pinfunction "IO_L8N_T1_AD10N_15_G20") (pintype "bidirectional"))
    )
    (net (code "171") (name "unconnected-(U4B-IO_L8P_T1_AD10P_15-PadH20)") (class "Default")
      (node (ref "U4") (pin "H20") (pinfunction "IO_L8P_T1_AD10P_15_H20") (pintype "bidirectional"))
    )
    (net (code "172") (name "unconnected-(U4B-IO_L9N_T1_DQS_AD3N_15-PadK22)") (class "Default")
      (node (ref "U4") (pin "K22") (pinfunction "IO_L9N_T1_DQS_AD3N_15_K22") (pintype "bidirectional"))
    )
    (net (code "173") (name "unconnected-(U4B-IO_L9P_T1_DQS_AD3P_15-PadK21)") (class "Default")
      (node (ref "U4") (pin "K21") (pinfunction "IO_L9P_T1_DQS_AD3P_15_K21") (pintype "bidirectional"))
    )
    (net (code "174") (name "unconnected-(U4B-IO_L10N_T1_AD11N_15-PadL21)") (class "Default")
      (node (ref "U4") (pin "L21") (pinfunction "IO_L10N_T1_AD11N_15_L21") (pintype "bidirectional"))
    )
    (net (code "175") (name "unconnected-(U4B-IO_L10P_T1_AD11P_15-PadM21)") (class "Default")
      (node (ref "U4") (pin "M21") (pinfunction "IO_L10P_T1_AD11P_15_M21") (pintype "bidirectional"))
    )
    (net (code "176") (name "unconnected-(U4B-IO_L11N_T1_SRCC_15-PadJ21)") (class "Default")
      (node (ref "U4") (pin "J21") (pinfunction "IO_L11N_T1_SRCC_15_J21") (pintype "bidirectional"))
    )
    (net (code "177") (name "unconnected-(U4B-IO_L11P_T1_SRCC_15-PadJ20)") (class "Default")
      (node (ref "U4") (pin "J20") (pinfunction "IO_L11P_T1_SRCC_15_J20") (pintype "bidirectional"))
    )
    (net (code "178") (name "unconnected-(U4B-IO_L12N_T1_MRCC_15-PadH19)") (class "Default")
      (node (ref "U4") (pin "H19") (pinfunction "IO_L12N_T1_MRCC_15_H19") (pintype "bidirectional"))
    )
    (net (code "179") (name "unconnected-(U4B-IO_L13N_T2_MRCC_15-PadK19)") (class "Default")
      (node (ref "U4") (pin "K19") (pinfunction "IO_L13N_T2_MRCC_15_K19") (pintype "bidirectional"))
    )
    (net (code "180") (name "unconnected-(U4B-IO_L13P_T2_MRCC_15-PadK18)") (class "Default")
      (node (ref "U4") (pin "K18") (pinfunction "IO_L13P_T2_MRCC_15_K18") (pintype "bidirectional"))
    )
    (net (code "181") (name "unconnected-(U4B-IO_L14N_T2_SRCC_15-PadL20)") (class "Default")
      (node (ref "U4") (pin "L20") (pinfunction "IO_L14N_T2_SRCC_15_L20") (pintype "bidirectional"))
    )
    (net (code "182") (name "unconnected-(U4B-IO_L14P_T2_SRCC_15-PadL19)") (class "Default")
      (node (ref "U4") (pin "L19") (pinfunction "IO_L14P_T2_SRCC_15_L19") (pintype "bidirectional"))
    )
    (net (code "183") (name "unconnected-(U4B-IO_L15N_T2_DQS_ADV_B_15-PadM22)") (class "Default")
      (node (ref "U4") (pin "M22") (pinfunction "IO_L15N_T2_DQS_ADV_B_15_M22") (pintype "bidirectional"))
    )
    (net (code "184") (name "unconnected-(U4B-IO_L15P_T2_DQS_15-PadN22)") (class "Default")
      (node (ref "U4") (pin "N22") (pinfunction "IO_L15P_T2_DQS_15_N22") (pintype "bidirectional"))
    )
    (net (code "185") (name "unconnected-(U4B-IO_L16N_T2_A27_15-PadL18)") (class "Default")
      (node (ref "U4") (pin "L18") (pinfunction "IO_L16N_T2_A27_15_L18") (pintype "bidirectional"))
    )
    (net (code "186") (name "unconnected-(U4B-IO_L16P_T2_A28_15-PadM18)") (class "Default")
      (node (ref "U4") (pin "M18") (pinfunction "IO_L16P_T2_A28_15_M18") (pintype "bidirectional"))
    )
    (net (code "187") (name "unconnected-(U4B-IO_L17N_T2_A25_15-PadN19)") (class "Default")
      (node (ref "U4") (pin "N19") (pinfunction "IO_L17N_T2_A25_15_N19") (pintype "bidirectional"))
    )
    (net (code "188") (name "unconnected-(U4B-IO_L17P_T2_A26_15-PadN18)") (class "Default")
      (node (ref "U4") (pin "N18") (pinfunction "IO_L17P_T2_A26_15_N18") (pintype "bidirectional"))
    )
    (net (code "189") (name "unconnected-(U4B-IO_L18N_T2_A23_15-PadM20)") (class "Default")
      (node (ref "U4") (pin "M20") (pinfunction "IO_L18N_T2_A23_15_M20") (pintype "bidirectional"))
    )
    (net (code "190") (name "unconnected-(U4B-IO_L18P_T2_A24_15-PadN20)") (class "Default")
      (node (ref "U4") (pin "N20") (pinfunction "IO_L18P_T2_A24_15_N20") (pintype "bidirectional"))
    )
    (net (code "191") (name "unconnected-(U4B-IO_L19N_T3_A21_VREF_15-PadK14)") (class "Default")
      (node (ref "U4") (pin "K14") (pinfunction "IO_L19N_T3_A21_VREF_15_K14") (pintype "bidirectional"))
    )
    (net (code "192") (name "unconnected-(U4B-IO_L19P_T3_A22_15-PadK13)") (class "Default")
      (node (ref "U4") (pin "K13") (pinfunction "IO_L19P_T3_A22_15_K13") (pintype "bidirectional"))
    )
    (net (code "193") (name "unconnected-(U4B-IO_L20N_T3_A19_15-PadL13)") (class "Default")
      (node (ref "U4") (pin "L13") (pinfunction "IO_L20N_T3_A19_15_L13") (pintype "bidirectional"))
    )
    (net (code "194") (name "unconnected-(U4B-IO_L20P_T3_A20_15-PadM13)") (class "Default")
      (node (ref "U4") (pin "M13") (pinfunction "IO_L20P_T3_A20_15_M13") (pintype "bidirectional"))
    )
    (net (code "195") (name "unconnected-(U4B-IO_L21N_T3_DQS_A18_15-PadJ17)") (class "Default")
      (node (ref "U4") (pin "J17") (pinfunction "IO_L21N_T3_DQS_A18_15_J17") (pintype "bidirectional"))
    )
    (net (code "196") (name "unconnected-(U4B-IO_L21P_T3_DQS_15-PadK17)") (class "Default")
      (node (ref "U4") (pin "K17") (pinfunction "IO_L21P_T3_DQS_15_K17") (pintype "bidirectional"))
    )
    (net (code "197") (name "unconnected-(U4B-IO_L22N_T3_A16_15-PadL15)") (class "Default")
      (node (ref "U4") (pin "L15") (pinfunction "IO_L22N_T3_A16_15_L15") (pintype "bidirectional"))
    )
    (net (code "198") (name "unconnected-(U4B-IO_L22P_T3_A17_15-PadL14)") (class "Default")
      (node (ref "U4") (pin "L14") (pinfunction "IO_L22P_T3_A17_15_L14") (pintype "bidirectional"))
    )
    (net (code "199") (name "unconnected-(U4B-IO_L23N_T3_FWE_B_15-PadK16)") (class "Default")
      (node (ref "U4") (pin "K16") (pinfunction "IO_L23N_T3_FWE_B_15_K16") (pintype "bidirectional"))
    )
    (net (code "200") (name "unconnected-(U4B-IO_L23P_T3_FOE_B_15-PadL16)") (class "Default")
      (node (ref "U4") (pin "L16") (pinfunction "IO_L23P_T3_FOE_B_15_L16") (pintype "bidirectional"))
    )
    (net (code "201") (name "unconnected-(U4B-IO_L24N_T3_RS0_15-PadM16)") (class "Default")
      (node (ref "U4") (pin "M16") (pinfunction "IO_L24N_T3_RS0_15_M16") (pintype "bidirectional"))
    )
    (net (code "202") (name "unconnected-(U4B-IO_L24P_T3_RS1_15-PadM15)") (class "Default")
      (node (ref "U4") (pin "M15") (pinfunction "IO_L24P_T3_RS1_15_M15") (pintype "bidirectional"))
    )
    (net (code "203") (name "unconnected-(U4E-IO_0_35-PadF4)") (class "Default")
      (node (ref "U4") (pin "F4") (pinfunction "IO_0_35_F4") (pintype "bidirectional"))
    )
    (net (code "204") (name "unconnected-(U4E-IO_L3P_T0_DQS_AD5P_35-PadE1)") (class "Default")
      (node (ref "U4") (pin "E1") (pinfunction "IO_L3P_T0_DQS_AD5P_35_E1") (pintype "bidirectional"))
    )
    (net (code "205") (name "unconnected-(U4E-IO_L4P_T0_35-PadE2)") (class "Default")
      (node (ref "U4") (pin "E2") (pinfunction "IO_L4P_T0_35_E2") (pintype "bidirectional"))
    )
    (net (code "206") (name "unconnected-(U4E-IO_L5N_T0_AD13N_35-PadF1)") (class "Default")
      (node (ref "U4") (pin "F1") (pinfunction "IO_L5N_T0_AD13N_35_F1") (pintype "bidirectional"))
    )
    (net (code "207") (name "unconnected-(U4E-IO_L6N_T0_VREF_35-PadE3)") (class "Default")
      (node (ref "U4") (pin "E3") (pinfunction "IO_L6N_T0_VREF_35_E3") (pintype "bidirectional"))
    )
    (net (code "208") (name "unconnected-(U4E-IO_L6P_T0_35-PadF3)") (class "Default")
      (node (ref "U4") (pin "F3") (pinfunction "IO_L6P_T0_35_F3") (pintype "bidirectional"))
    )
    (net (code "209") (name "unconnected-(U4L-NC-PadAA9)") (class "Default")
      (node (ref "U4") (pin "AA9") (pinfunction "NC_AA9") (pintype "passive"))
    )
    (net (code "210") (name "unconnected-(U4L-NC-PadAA10)") (class "Default")
      (node (ref "U4") (pin "AA10") (pinfunction "NC_AA10") (pintype "passive"))
    )
    (net (code "211") (name "unconnected-(U4L-NC-PadAA11)") (class "Default")
      (node (ref "U4") (pin "AA11") (pinfunction "NC_AA11") (pintype "passive"))
    )
    (net (code "212") (name "unconnected-(U4L-NC-PadAA13)") (class "Default")
      (node (ref "U4") (pin "AA13") (pinfunction "NC_AA13") (pintype "passive"))
    )
    (net (code "213") (name "unconnected-(U4L-NC-PadAA14)") (class "Default")
      (node (ref "U4") (pin "AA14") (pinfunction "NC_AA14") (pintype "passive"))
    )
    (net (code "214") (name "unconnected-(U4L-NC-PadAA15)") (class "Default")
      (node (ref "U4") (pin "AA15") (pinfunction "NC_AA15") (pintype "passive"))
    )
    (net (code "215") (name "unconnected-(U4L-NC-PadAA16)") (class "Default")
      (node (ref "U4") (pin "AA16") (pinfunction "NC_AA16") (pintype "passive"))
    )
    (net (code "216") (name "unconnected-(U4L-NC-PadAB10)") (class "Default")
      (node (ref "U4") (pin "AB10") (pinfunction "NC_AB10") (pintype "passive"))
    )
    (net (code "217") (name "unconnected-(U4L-NC-PadAB11)") (class "Default")
      (node (ref "U4") (pin "AB11") (pinfunction "NC_AB11") (pintype "passive"))
    )
    (net (code "218") (name "unconnected-(U4L-NC-PadAB12)") (class "Default")
      (node (ref "U4") (pin "AB12") (pinfunction "NC_AB12") (pintype "passive"))
    )
    (net (code "219") (name "unconnected-(U4L-NC-PadAB13)") (class "Default")
      (node (ref "U4") (pin "AB13") (pinfunction "NC_AB13") (pintype "passive"))
    )
    (net (code "220") (name "unconnected-(U4L-NC-PadAB15)") (class "Default")
      (node (ref "U4") (pin "AB15") (pinfunction "NC_AB15") (pintype "passive"))
    )
    (net (code "221") (name "unconnected-(U4L-NC-PadAB16)") (class "Default")
      (node (ref "U4") (pin "AB16") (pinfunction "NC_AB16") (pintype "passive"))
    )
    (net (code "222") (name "unconnected-(U4L-NC-PadAB17)") (class "Default")
      (node (ref "U4") (pin "AB17") (pinfunction "NC_AB17") (pintype "passive"))
    )
    (net (code "223") (name "unconnected-(U4L-NC-PadT14)") (class "Default")
      (node (ref "U4") (pin "T14") (pinfunction "NC_T14") (pintype "passive"))
    )
    (net (code "224") (name "unconnected-(U4L-NC-PadT15)") (class "Default")
      (node (ref "U4") (pin "T15") (pinfunction "NC_T15") (pintype "passive"))
    )
    (net (code "225") (name "unconnected-(U4L-NC-PadT16)") (class "Default")
      (node (ref "U4") (pin "T16") (pinfunction "NC_T16") (pintype "passive"))
    )
    (net (code "226") (name "unconnected-(U4L-NC-PadU15)") (class "Default")
      (node (ref "U4") (pin "U15") (pinfunction "NC_U15") (pintype "passive"))
    )
    (net (code "227") (name "unconnected-(U4L-NC-PadU16)") (class "Default")
      (node (ref "U4") (pin "U16") (pinfunction "NC_U16") (pintype "passive"))
    )
    (net (code "228") (name "unconnected-(U4L-NC-PadV10)") (class "Default")
      (node (ref "U4") (pin "V10") (pinfunction "NC_V10") (pintype "passive"))
    )
    (net (code "229") (name "unconnected-(U4L-NC-PadV13)") (class "Default")
      (node (ref "U4") (pin "V13") (pinfunction "NC_V13") (pintype "passive"))
    )
    (net (code "230") (name "unconnected-(U4L-NC-PadV14)") (class "Default")
      (node (ref "U4") (pin "V14") (pinfunction "NC_V14") (pintype "passive"))
    )
    (net (code "231") (name "unconnected-(U4L-NC-PadV15)") (class "Default")
      (node (ref "U4") (pin "V15") (pinfunction "NC_V15") (pintype "passive"))
    )
    (net (code "232") (name "unconnected-(U4L-NC-PadW10)") (class "Default")
      (node (ref "U4") (pin "W10") (pinfunction "NC_W10") (pintype "passive"))
    )
    (net (code "233") (name "unconnected-(U4L-NC-PadW11)") (class "Default")
      (node (ref "U4") (pin "W11") (pinfunction "NC_W11") (pintype "passive"))
    )
    (net (code "234") (name "unconnected-(U4L-NC-PadW12)") (class "Default")
      (node (ref "U4") (pin "W12") (pinfunction "NC_W12") (pintype "passive"))
    )
    (net (code "235") (name "unconnected-(U4L-NC-PadW14)") (class "Default")
      (node (ref "U4") (pin "W14") (pinfunction "NC_W14") (pintype "passive"))
    )
    (net (code "236") (name "unconnected-(U4L-NC-PadW15)") (class "Default")
      (node (ref "U4") (pin "W15") (pinfunction "NC_W15") (pintype "passive"))
    )
    (net (code "237") (name "unconnected-(U4L-NC-PadW16)") (class "Default")
      (node (ref "U4") (pin "W16") (pinfunction "NC_W16") (pintype "passive"))
    )
    (net (code "238") (name "unconnected-(U4L-NC-PadY11)") (class "Default")
      (node (ref "U4") (pin "Y11") (pinfunction "NC_Y11") (pintype "passive"))
    )
    (net (code "239") (name "unconnected-(U4L-NC-PadY12)") (class "Default")
      (node (ref "U4") (pin "Y12") (pinfunction "NC_Y12") (pintype "passive"))
    )
    (net (code "240") (name "unconnected-(U4L-NC-PadY13)") (class "Default")
      (node (ref "U4") (pin "Y13") (pinfunction "NC_Y13") (pintype "passive"))
    )
    (net (code "241") (name "unconnected-(U4L-NC-PadY14)") (class "Default")
      (node (ref "U4") (pin "Y14") (pinfunction "NC_Y14") (pintype "passive"))
    )
    (net (code "242") (name "unconnected-(U4L-NC-PadY16)") (class "Default")
      (node (ref "U4") (pin "Y16") (pinfunction "NC_Y16") (pintype "passive"))
    )
    (net (code "243") (name "unconnected-(U4L-NC-PadY17)") (class "Default")
      (node (ref "U4") (pin "Y17") (pinfunction "NC_Y17") (pintype "passive"))
    )
  )
)
